# Schaltplan_Power_Amp.net
KiCad netlist of a schematic drawn in EAGLE
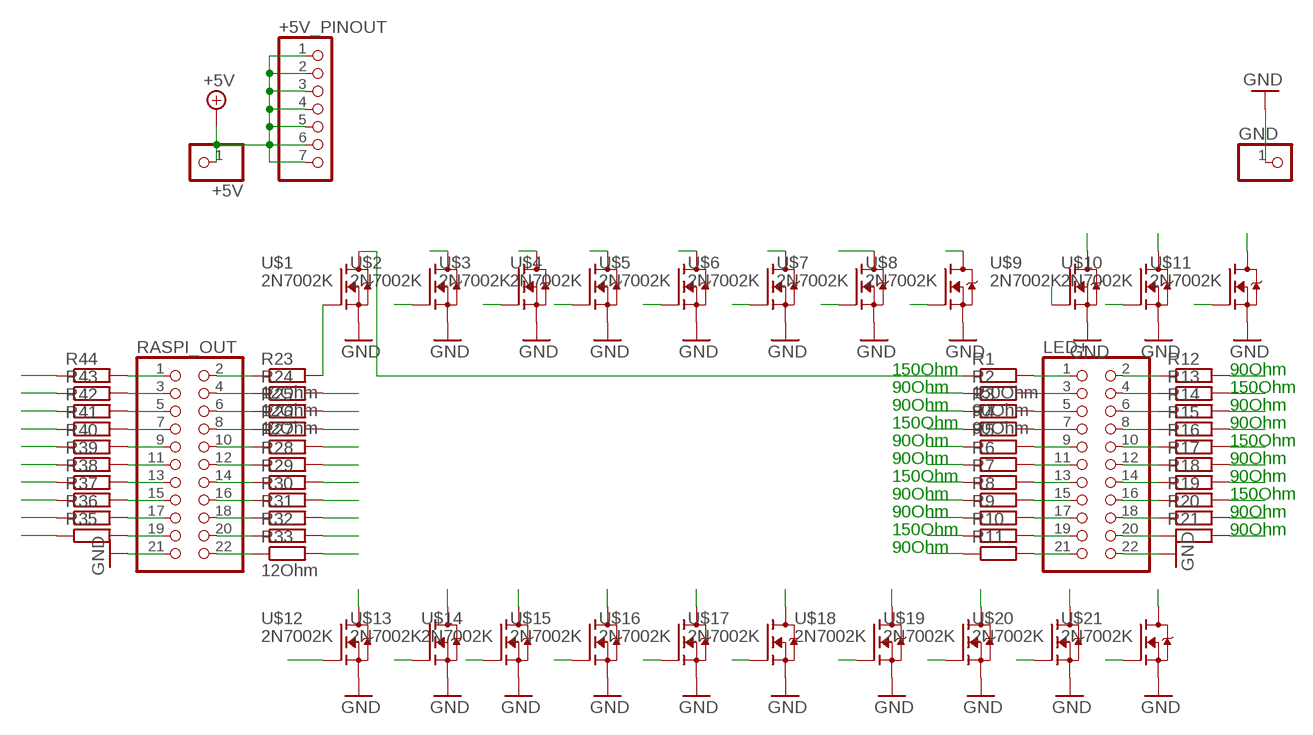
[diagram p0: schematic, sheet 1]

(export (version "E")
  (design (tool "Eeschema 10.0.6"))
  (components
    (comp (ref "+5V")
      (value "PINHD-1X1")
      (footprint "eagle-import:1X01")
      (libsource (lib "eagle-import") (part "PINHD-1X1"))
    )
    (comp (ref "+5V_PINOUT")
      (value "PINHD-1X7")
      (footprint "eagle-import:1X07")
      (libsource (lib "eagle-import") (part "PINHD-1X7"))
    )
    (comp (ref "GND")
      (value "PINHD-1X1")
      (footprint "eagle-import:1X01")
      (libsource (lib "eagle-import") (part "PINHD-1X1"))
    )
    (comp (ref "LED+")
      (value "PINHD-2X11")
      (footprint "eagle-import:2X11")
      (libsource (lib "eagle-import") (part "PINHD-2X11"))
    )
    (comp (ref "R1")
      (value "150Ohm")
      (footprint "eagle-import:M1206")
      (libsource (lib "eagle-import") (part "R-EU_M1206"))
    )
    (comp (ref "R2")
      (value "90Ohm")
      (footprint "eagle-import:M1206")
      (libsource (lib "eagle-import") (part "R-EU_M1206"))
    )
    (comp (ref "R3")
      (value "90Ohm")
      (footprint "eagle-import:M1206")
      (libsource (lib "eagle-import") (part "R-EU_M1206"))
    )
    (comp (ref "R4")
      (value "R-EU_M1206")
      (footprint "eagle-import:M1206")
      (libsource (lib "eagle-import") (part "R-EU_M1206"))
    )
    (comp (ref "R5")
      (value "R-EU_M1206")
      (footprint "eagle-import:M1206")
      (libsource (lib "eagle-import") (part "R-EU_M1206"))
    )
    (comp (ref "R6")
      (value "R-EU_M1206")
      (footprint "eagle-import:M1206")
      (libsource (lib "eagle-import") (part "R-EU_M1206"))
    )
    (comp (ref "R7")
      (value "R-EU_M1206")
      (footprint "eagle-import:M1206")
      (libsource (lib "eagle-import") (part "R-EU_M1206"))
    )
    (comp (ref "R8")
      (value "R-EU_M1206")
      (footprint "eagle-import:M1206")
      (libsource (lib "eagle-import") (part "R-EU_M1206"))
    )
    (comp (ref "R9")
      (value "R-EU_M1206")
      (footprint "eagle-import:M1206")
      (libsource (lib "eagle-import") (part "R-EU_M1206"))
    )
    (comp (ref "R10")
      (value "R-EU_M1206")
      (footprint "eagle-import:M1206")
      (libsource (lib "eagle-import") (part "R-EU_M1206"))
    )
    (comp (ref "R11")
      (value "R-EU_M1206")
      (footprint "eagle-import:M1206")
      (libsource (lib "eagle-import") (part "R-EU_M1206"))
    )
    (comp (ref "R12")
      (value "R-EU_M1206")
      (footprint "eagle-import:M1206")
      (libsource (lib "eagle-import") (part "R-EU_M1206"))
    )
    (comp (ref "R13")
      (value "R-EU_M1206")
      (footprint "eagle-import:M1206")
      (libsource (lib "eagle-import") (part "R-EU_M1206"))
    )
    (comp (ref "R14")
      (value "R-EU_M1206")
      (footprint "eagle-import:M1206")
      (libsource (lib "eagle-import") (part "R-EU_M1206"))
    )
    (comp (ref "R15")
      (value "R-EU_M1206")
      (footprint "eagle-import:M1206")
      (libsource (lib "eagle-import") (part "R-EU_M1206"))
    )
    (comp (ref "R16")
      (value "R-EU_M1206")
      (footprint "eagle-import:M1206")
      (libsource (lib "eagle-import") (part "R-EU_M1206"))
    )
    (comp (ref "R17")
      (value "R-EU_M1206")
      (footprint "eagle-import:M1206")
      (libsource (lib "eagle-import") (part "R-EU_M1206"))
    )
    (comp (ref "R18")
      (value "R-EU_M1206")
      (footprint "eagle-import:M1206")
      (libsource (lib "eagle-import") (part "R-EU_M1206"))
    )
    (comp (ref "R19")
      (value "R-EU_M1206")
      (footprint "eagle-import:M1206")
      (libsource (lib "eagle-import") (part "R-EU_M1206"))
    )
    (comp (ref "R20")
      (value "R-EU_M1206")
      (footprint "eagle-import:M1206")
      (libsource (lib "eagle-import") (part "R-EU_M1206"))
    )
    (comp (ref "R21")
      (value "R-EU_M1206")
      (footprint "eagle-import:M1206")
      (libsource (lib "eagle-import") (part "R-EU_M1206"))
    )
    (comp (ref "R23")
      (value "12Ohm")
      (footprint "eagle-import:M1206")
      (libsource (lib "eagle-import") (part "R-EU_M1206"))
    )
    (comp (ref "R24")
      (value "12Ohm")
      (footprint "eagle-import:M1206")
      (libsource (lib "eagle-import") (part "R-EU_M1206"))
    )
    (comp (ref "R25")
      (value "12Ohm")
      (footprint "eagle-import:M1206")
      (libsource (lib "eagle-import") (part "R-EU_M1206"))
    )
    (comp (ref "R26")
      (value "R-EU_M1206")
      (footprint "eagle-import:M1206")
      (libsource (lib "eagle-import") (part "R-EU_M1206"))
    )
    (comp (ref "R27")
      (value "R-EU_M1206")
      (footprint "eagle-import:M1206")
      (libsource (lib "eagle-import") (part "R-EU_M1206"))
    )
    (comp (ref "R28")
      (value "R-EU_M1206")
      (footprint "eagle-import:M1206")
      (libsource (lib "eagle-import") (part "R-EU_M1206"))
    )
    (comp (ref "R29")
      (value "R-EU_M1206")
      (footprint "eagle-import:M1206")
      (libsource (lib "eagle-import") (part "R-EU_M1206"))
    )
    (comp (ref "R30")
      (value "R-EU_M1206")
      (footprint "eagle-import:M1206")
      (libsource (lib "eagle-import") (part "R-EU_M1206"))
    )
    (comp (ref "R31")
      (value "R-EU_M1206")
      (footprint "eagle-import:M1206")
      (libsource (lib "eagle-import") (part "R-EU_M1206"))
    )
    (comp (ref "R32")
      (value "R-EU_M1206")
      (footprint "eagle-import:M1206")
      (libsource (lib "eagle-import") (part "R-EU_M1206"))
    )
    (comp (ref "R33")
      (value "12Ohm")
      (footprint "eagle-import:M1206")
      (libsource (lib "eagle-import") (part "R-EU_M1206"))
    )
    (comp (ref "R35")
      (value "R-EU_M1206")
      (footprint "eagle-import:M1206")
      (libsource (lib "eagle-import") (part "R-EU_M1206"))
    )
    (comp (ref "R36")
      (value "R-EU_M1206")
      (footprint "eagle-import:M1206")
      (libsource (lib "eagle-import") (part "R-EU_M1206"))
    )
    (comp (ref "R37")
      (value "R-EU_M1206")
      (footprint "eagle-import:M1206")
      (libsource (lib "eagle-import") (part "R-EU_M1206"))
    )
    (comp (ref "R38")
      (value "R-EU_M1206")
      (footprint "eagle-import:M1206")
      (libsource (lib "eagle-import") (part "R-EU_M1206"))
    )
    (comp (ref "R39")
      (value "R-EU_M1206")
      (footprint "eagle-import:M1206")
      (libsource (lib "eagle-import") (part "R-EU_M1206"))
    )
    (comp (ref "R40")
      (value "R-EU_M1206")
      (footprint "eagle-import:M1206")
      (libsource (lib "eagle-import") (part "R-EU_M1206"))
    )
    (comp (ref "R41")
      (value "R-EU_M1206")
      (footprint "eagle-import:M1206")
      (libsource (lib "eagle-import") (part "R-EU_M1206"))
    )
    (comp (ref "R42")
      (value "R-EU_M1206")
      (footprint "eagle-import:M1206")
      (libsource (lib "eagle-import") (part "R-EU_M1206"))
    )
    (comp (ref "R43")
      (value "R-EU_M1206")
      (footprint "eagle-import:M1206")
      (libsource (lib "eagle-import") (part "R-EU_M1206"))
    )
    (comp (ref "R44")
      (value "R-EU_M1206")
      (footprint "eagle-import:M1206")
      (libsource (lib "eagle-import") (part "R-EU_M1206"))
    )
    (comp (ref "RASPI_OUT")
      (value "PINHD-2X11")
      (footprint "eagle-import:2X11")
      (libsource (lib "eagle-import") (part "PINHD-2X11"))
    )
    (comp (ref "U$1")
      (value "2N7002K")
      (footprint "eagle-import:SOT23")
      (libsource (lib "eagle-import") (part "2N7002K"))
    )
    (comp (ref "U$2")
      (value "2N7002K")
      (footprint "eagle-import:SOT23")
      (libsource (lib "eagle-import") (part "2N7002K"))
    )
    (comp (ref "U$3")
      (value "2N7002K")
      (footprint "eagle-import:SOT23")
      (libsource (lib "eagle-import") (part "2N7002K"))
    )
    (comp (ref "U$4")
      (value "2N7002K")
      (footprint "eagle-import:SOT23")
      (libsource (lib "eagle-import") (part "2N7002K"))
    )
    (comp (ref "U$5")
      (value "2N7002K")
      (footprint "eagle-import:SOT23")
      (libsource (lib "eagle-import") (part "2N7002K"))
    )
    (comp (ref "U$6")
      (value "2N7002K")
      (footprint "eagle-import:SOT23")
      (libsource (lib "eagle-import") (part "2N7002K"))
    )
    (comp (ref "U$7")
      (value "2N7002K")
      (footprint "eagle-import:SOT23")
      (libsource (lib "eagle-import") (part "2N7002K"))
    )
    (comp (ref "U$8")
      (value "2N7002K")
      (footprint "eagle-import:SOT23")
      (libsource (lib "eagle-import") (part "2N7002K"))
    )
    (comp (ref "U$9")
      (value "2N7002K")
      (footprint "eagle-import:SOT23")
      (libsource (lib "eagle-import") (part "2N7002K"))
    )
    (comp (ref "U$10")
      (value "2N7002K")
      (footprint "eagle-import:SOT23")
      (libsource (lib "eagle-import") (part "2N7002K"))
    )
    (comp (ref "U$11")
      (value "2N7002K")
      (footprint "eagle-import:SOT23")
      (libsource (lib "eagle-import") (part "2N7002K"))
    )
    (comp (ref "U$12")
      (value "2N7002K")
      (footprint "eagle-import:SOT23")
      (libsource (lib "eagle-import") (part "2N7002K"))
    )
    (comp (ref "U$13")
      (value "2N7002K")
      (footprint "eagle-import:SOT23")
      (libsource (lib "eagle-import") (part "2N7002K"))
    )
    (comp (ref "U$14")
      (value "2N7002K")
      (footprint "eagle-import:SOT23")
      (libsource (lib "eagle-import") (part "2N7002K"))
    )
    (comp (ref "U$15")
      (value "2N7002K")
      (footprint "eagle-import:SOT23")
      (libsource (lib "eagle-import") (part "2N7002K"))
    )
    (comp (ref "U$16")
      (value "2N7002K")
      (footprint "eagle-import:SOT23")
      (libsource (lib "eagle-import") (part "2N7002K"))
    )
    (comp (ref "U$17")
      (value "2N7002K")
      (footprint "eagle-import:SOT23")
      (libsource (lib "eagle-import") (part "2N7002K"))
    )
    (comp (ref "U$18")
      (value "2N7002K")
      (footprint "eagle-import:SOT23")
      (libsource (lib "eagle-import") (part "2N7002K"))
    )
    (comp (ref "U$19")
      (value "2N7002K")
      (footprint "eagle-import:SOT23")
      (libsource (lib "eagle-import") (part "2N7002K"))
    )
    (comp (ref "U$20")
      (value "2N7002K")
      (footprint "eagle-import:SOT23")
      (libsource (lib "eagle-import") (part "2N7002K"))
    )
    (comp (ref "U$21")
      (value "2N7002K")
      (footprint "eagle-import:SOT23")
      (libsource (lib "eagle-import") (part "2N7002K"))
    )
  )
  (nets
    (net (code "1") (name "+5V") (class "Default")
      (node (ref "+5V") (pin "1") (pinfunction "1_1") (pintype "passive"))
      (node (ref "+5V_PINOUT") (pin "1") (pinfunction "1_1") (pintype "passive"))
      (node (ref "+5V_PINOUT") (pin "2") (pinfunction "2_2") (pintype "passive"))
      (node (ref "+5V_PINOUT") (pin "3") (pinfunction "3_3") (pintype "passive"))
      (node (ref "+5V_PINOUT") (pin "4") (pinfunction "4_4") (pintype "passive"))
      (node (ref "+5V_PINOUT") (pin "5") (pinfunction "5_5") (pintype "passive"))
      (node (ref "+5V_PINOUT") (pin "6") (pinfunction "6_6") (pintype "passive"))
      (node (ref "+5V_PINOUT") (pin "7") (pinfunction "7_7") (pintype "passive"))
    )
    (net (code "2") (name "/DRAIN2") (class "Default")
      (node (ref "R2") (pin "1") (pinfunction "1_1") (pintype "passive"))
      (node (ref "U$2") (pin "3") (pinfunction "D_3") (pintype "passive"))
    )
    (net (code "3") (name "/DRAIN3") (class "Default")
      (node (ref "R3") (pin "1") (pinfunction "1_1") (pintype "passive"))
      (node (ref "U$3") (pin "3") (pinfunction "D_3") (pintype "passive"))
    )
    (net (code "4") (name "/DRAIN4") (class "Default")
      (node (ref "R4") (pin "1") (pinfunction "1_1") (pintype "passive"))
      (node (ref "U$4") (pin "3") (pinfunction "D_3") (pintype "passive"))
    )
    (net (code "5") (name "/DRAIN5") (class "Default")
      (node (ref "R5") (pin "1") (pinfunction "1_1") (pintype "passive"))
      (node (ref "U$5") (pin "3") (pinfunction "D_3") (pintype "passive"))
    )
    (net (code "6") (name "/DRAIN6") (class "Default")
      (node (ref "R6") (pin "1") (pinfunction "1_1") (pintype "passive"))
      (node (ref "U$6") (pin "3") (pinfunction "D_3") (pintype "passive"))
    )
    (net (code "7") (name "/DRAIN7") (class "Default")
      (node (ref "R7") (pin "1") (pinfunction "1_1") (pintype "passive"))
      (node (ref "U$7") (pin "3") (pinfunction "D_3") (pintype "passive"))
    )
    (net (code "8") (name "/DRAIN8") (class "Default")
      (node (ref "R8") (pin "1") (pinfunction "1_1") (pintype "passive"))
      (node (ref "U$8") (pin "3") (pinfunction "D_3") (pintype "passive"))
    )
    (net (code "9") (name "/DRAIN9") (class "Default")
      (node (ref "R9") (pin "1") (pinfunction "1_1") (pintype "passive"))
      (node (ref "U$9") (pin "3") (pinfunction "D_3") (pintype "passive"))
    )
    (net (code "10") (name "/DRAIN10") (class "Default")
      (node (ref "R10") (pin "1") (pinfunction "1_1") (pintype "passive"))
      (node (ref "U$10") (pin "3") (pinfunction "D_3") (pintype "passive"))
    )
    (net (code "11") (name "/DRAIN11") (class "Default")
      (node (ref "R11") (pin "1") (pinfunction "1_1") (pintype "passive"))
      (node (ref "U$11") (pin "3") (pinfunction "D_3") (pintype "passive"))
    )
    (net (code "12") (name "/DRAIN12") (class "Default")
      (node (ref "R12") (pin "2") (pinfunction "2_2") (pintype "passive"))
      (node (ref "U$12") (pin "3") (pinfunction "D_3") (pintype "passive"))
    )
    (net (code "13") (name "/DRAIN13") (class "Default")
      (node (ref "R13") (pin "2") (pinfunction "2_2") (pintype "passive"))
      (node (ref "U$13") (pin "3") (pinfunction "D_3") (pintype "passive"))
    )
    (net (code "14") (name "/DRAIN14") (class "Default")
      (node (ref "R14") (pin "2") (pinfunction "2_2") (pintype "passive"))
      (node (ref "U$14") (pin "3") (pinfunction "D_3") (pintype "passive"))
    )
    (net (code "15") (name "/DRAIN15") (class "Default")
      (node (ref "R15") (pin "2") (pinfunction "2_2") (pintype "passive"))
      (node (ref "U$15") (pin "3") (pinfunction "D_3") (pintype "passive"))
    )
    (net (code "16") (name "/DRAIN16") (class "Default")
      (node (ref "R16") (pin "2") (pinfunction "2_2") (pintype "passive"))
      (node (ref "U$16") (pin "3") (pinfunction "D_3") (pintype "passive"))
    )
    (net (code "17") (name "/DRAIN17") (class "Default")
      (node (ref "R17") (pin "2") (pinfunction "2_2") (pintype "passive"))
      (node (ref "U$17") (pin "3") (pinfunction "D_3") (pintype "passive"))
    )
    (net (code "18") (name "/DRAIN18") (class "Default")
      (node (ref "R18") (pin "2") (pinfunction "2_2") (pintype "passive"))
      (node (ref "U$18") (pin "3") (pinfunction "D_3") (pintype "passive"))
    )
    (net (code "19") (name "/DRAIN19") (class "Default")
      (node (ref "R19") (pin "2") (pinfunction "2_2") (pintype "passive"))
      (node (ref "U$19") (pin "3") (pinfunction "D_3") (pintype "passive"))
    )
    (net (code "20") (name "/DRAIN20") (class "Default")
      (node (ref "R20") (pin "2") (pinfunction "2_2") (pintype "passive"))
      (node (ref "U$20") (pin "3") (pinfunction "D_3") (pintype "passive"))
    )
    (net (code "21") (name "/DRAIN21") (class "Default")
      (node (ref "R21") (pin "2") (pinfunction "2_2") (pintype "passive"))
      (node (ref "U$21") (pin "3") (pinfunction "D_3") (pintype "passive"))
    )
    (net (code "22") (name "/GATE2") (class "Default")
      (node (ref "R24") (pin "2") (pinfunction "2_2") (pintype "passive"))
      (node (ref "U$2") (pin "1") (pinfunction "G_1") (pintype "passive"))
    )
    (net (code "23") (name "/GATE3") (class "Default")
      (node (ref "R25") (pin "2") (pinfunction "2_2") (pintype "passive"))
      (node (ref "U$3") (pin "1") (pinfunction "G_1") (pintype "passive"))
    )
    (net (code "24") (name "/GATE4") (class "Default")
      (node (ref "R26") (pin "2") (pinfunction "2_2") (pintype "passive"))
      (node (ref "U$4") (pin "1") (pinfunction "G_1") (pintype "passive"))
    )
    (net (code "25") (name "/GATE5") (class "Default")
      (node (ref "R27") (pin "2") (pinfunction "2_2") (pintype "passive"))
      (node (ref "U$5") (pin "1") (pinfunction "G_1") (pintype "passive"))
    )
    (net (code "26") (name "/GATE6") (class "Default")
      (node (ref "R28") (pin "2") (pinfunction "2_2") (pintype "passive"))
      (node (ref "U$6") (pin "1") (pinfunction "G_1") (pintype "passive"))
    )
    (net (code "27") (name "/GATE7") (class "Default")
      (node (ref "R29") (pin "2") (pinfunction "2_2") (pintype "passive"))
      (node (ref "U$7") (pin "1") (pinfunction "G_1") (pintype "passive"))
    )
    (net (code "28") (name "/GATE8") (class "Default")
      (node (ref "R30") (pin "2") (pinfunction "2_2") (pintype "passive"))
      (node (ref "U$8") (pin "1") (pinfunction "G_1") (pintype "passive"))
    )
    (net (code "29") (name "/GATE9") (class "Default")
      (node (ref "R31") (pin "2") (pinfunction "2_2") (pintype "passive"))
      (node (ref "U$9") (pin "1") (pinfunction "G_1") (pintype "passive"))
    )
    (net (code "30") (name "/GATE10") (class "Default")
      (node (ref "R32") (pin "2") (pinfunction "2_2") (pintype "passive"))
      (node (ref "U$10") (pin "1") (pinfunction "G_1") (pintype "passive"))
    )
    (net (code "31") (name "/GATE11") (class "Default")
      (node (ref "R33") (pin "2") (pinfunction "2_2") (pintype "passive"))
      (node (ref "U$11") (pin "1") (pinfunction "G_1") (pintype "passive"))
    )
    (net (code "32") (name "/GATE12") (class "Default")
      (node (ref "R44") (pin "1") (pinfunction "1_1") (pintype "passive"))
      (node (ref "U$12") (pin "1") (pinfunction "G_1") (pintype "passive"))
    )
    (net (code "33") (name "/GATE13") (class "Default")
      (node (ref "R43") (pin "1") (pinfunction "1_1") (pintype "passive"))
      (node (ref "U$13") (pin "1") (pinfunction "G_1") (pintype "passive"))
    )
    (net (code "34") (name "/GATE14") (class "Default")
      (node (ref "R42") (pin "1") (pinfunction "1_1") (pintype "passive"))
      (node (ref "U$14") (pin "1") (pinfunction "G_1") (pintype "passive"))
    )
    (net (code "35") (name "/GATE15") (class "Default")
      (node (ref "R41") (pin "1") (pinfunction "1_1") (pintype "passive"))
      (node (ref "U$15") (pin "1") (pinfunction "G_1") (pintype "passive"))
    )
    (net (code "36") (name "/GATE16") (class "Default")
      (node (ref "R40") (pin "1") (pinfunction "1_1") (pintype "passive"))
      (node (ref "U$16") (pin "1") (pinfunction "G_1") (pintype "passive"))
    )
    (net (code "37") (name "/GATE17") (class "Default")
      (node (ref "R39") (pin "1") (pinfunction "1_1") (pintype "passive"))
      (node (ref "U$17") (pin "1") (pinfunction "G_1") (pintype "passive"))
    )
    (net (code "38") (name "/GATE18") (class "Default")
      (node (ref "R38") (pin "1") (pinfunction "1_1") (pintype "passive"))
      (node (ref "U$18") (pin "1") (pinfunction "G_1") (pintype "passive"))
    )
    (net (code "39") (name "/GATE19") (class "Default")
      (node (ref "R37") (pin "1") (pinfunction "1_1") (pintype "passive"))
      (node (ref "U$19") (pin "1") (pinfunction "G_1") (pintype "passive"))
    )
    (net (code "40") (name "/GATE20") (class "Default")
      (node (ref "R36") (pin "1") (pinfunction "1_1") (pintype "passive"))
      (node (ref "U$20") (pin "1") (pinfunction "G_1") (pintype "passive"))
    )
    (net (code "41") (name "/GATE21") (class "Default")
      (node (ref "R35") (pin "1") (pinfunction "1_1") (pintype "passive"))
      (node (ref "U$21") (pin "1") (pinfunction "G_1") (pintype "passive"))
    )
    (net (code "42") (name "GND") (class "Default")
      (node (ref "GND") (pin "1") (pinfunction "1_1") (pintype "passive"))
      (node (ref "LED+") (pin "22") (pinfunction "22_22") (pintype "passive"))
      (node (ref "RASPI_OUT") (pin "21") (pinfunction "21_21") (pintype "passive"))
      (node (ref "U$1") (pin "2") (pinfunction "S_2") (pintype "passive"))
      (node (ref "U$10") (pin "2") (pinfunction "S_2") (pintype "passive"))
      (node (ref "U$11") (pin "2") (pinfunction "S_2") (pintype "passive"))
      (node (ref "U$12") (pin "2") (pinfunction "S_2") (pintype "passive"))
      (node (ref "U$13") (pin "2") (pinfunction "S_2") (pintype "passive"))
      (node (ref "U$14") (pin "2") (pinfunction "S_2") (pintype "passive"))
      (node (ref "U$15") (pin "2") (pinfunction "S_2") (pintype "passive"))
      (node (ref "U$16") (pin "2") (pinfunction "S_2") (pintype "passive"))
      (node (ref "U$17") (pin "2") (pinfunction "S_2") (pintype "passive"))
      (node (ref "U$18") (pin "2") (pinfunction "S_2") (pintype "passive"))
      (node (ref "U$19") (pin "2") (pinfunction "S_2") (pintype "passive"))
      (node (ref "U$2") (pin "2") (pinfunction "S_2") (pintype "passive"))
      (node (ref "U$20") (pin "2") (pinfunction "S_2") (pintype "passive"))
      (node (ref "U$21") (pin "2") (pinfunction "S_2") (pintype "passive"))
      (node (ref "U$3") (pin "2") (pinfunction "S_2") (pintype "passive"))
      (node (ref "U$4") (pin "2") (pinfunction "S_2") (pintype "passive"))
      (node (ref "U$5") (pin "2") (pinfunction "S_2") (pintype "passive"))
      (node (ref "U$6") (pin "2") (pinfunction "S_2") (pintype "passive"))
      (node (ref "U$7") (pin "2") (pinfunction "S_2") (pintype "passive"))
      (node (ref "U$8") (pin "2") (pinfunction "S_2") (pintype "passive"))
      (node (ref "U$9") (pin "2") (pinfunction "S_2") (pintype "passive"))
    )
    (net (code "43") (name "Net-(LED+-Pad1)") (class "Default")
      (node (ref "LED+") (pin "1") (pinfunction "1_1") (pintype "passive"))
      (node (ref "R1") (pin "2") (pinfunction "2_2") (pintype "passive"))
    )
    (net (code "44") (name "Net-(LED+-Pad2)") (class "Default")
      (node (ref "LED+") (pin "2") (pinfunction "2_2") (pintype "passive"))
      (node (ref "R12") (pin "1") (pinfunction "1_1") (pintype "passive"))
    )
    (net (code "45") (name "Net-(LED+-Pad3)") (class "Default")
      (node (ref "LED+") (pin "3") (pinfunction "3_3") (pintype "passive"))
      (node (ref "R2") (pin "2") (pinfunction "2_2") (pintype "passive"))
    )
    (net (code "46") (name "Net-(LED+-Pad4)") (class "Default")
      (node (ref "LED+") (pin "4") (pinfunction "4_4") (pintype "passive"))
      (node (ref "R13") (pin "1") (pinfunction "1_1") (pintype "passive"))
    )
    (net (code "47") (name "Net-(LED+-Pad5)") (class "Default")
      (node (ref "LED+") (pin "5") (pinfunction "5_5") (pintype "passive"))
      (node (ref "R3") (pin "2") (pinfunction "2_2") (pintype "passive"))
    )
    (net (code "48") (name "Net-(LED+-Pad6)") (class "Default")
      (node (ref "LED+") (pin "6") (pinfunction "6_6") (pintype "passive"))
      (node (ref "R14") (pin "1") (pinfunction "1_1") (pintype "passive"))
    )
    (net (code "49") (name "Net-(LED+-Pad7)") (class "Default")
      (node (ref "LED+") (pin "7") (pinfunction "7_7") (pintype "passive"))
      (node (ref "R4") (pin "2") (pinfunction "2_2") (pintype "passive"))
    )
    (net (code "50") (name "Net-(LED+-Pad8)") (class "Default")
      (node (ref "LED+") (pin "8") (pinfunction "8_8") (pintype "passive"))
      (node (ref "R15") (pin "1") (pinfunction "1_1") (pintype "passive"))
    )
    (net (code "51") (name "Net-(LED+-Pad9)") (class "Default")
      (node (ref "LED+") (pin "9") (pinfunction "9_9") (pintype "passive"))
      (node (ref "R5") (pin "2") (pinfunction "2_2") (pintype "passive"))
    )
    (net (code "52") (name "Net-(LED+-Pad10)") (class "Default")
      (node (ref "LED+") (pin "10") (pinfunction "10_10") (pintype "passive"))
      (node (ref "R16") (pin "1") (pinfunction "1_1") (pintype "passive"))
    )
    (net (code "53") (name "Net-(LED+-Pad11)") (class "Default")
      (node (ref "LED+") (pin "11") (pinfunction "11_11") (pintype "passive"))
      (node (ref "R6") (pin "2") (pinfunction "2_2") (pintype "passive"))
    )
    (net (code "54") (name "Net-(LED+-Pad12)") (class "Default")
      (node (ref "LED+") (pin "12") (pinfunction "12_12") (pintype "passive"))
      (node (ref "R17") (pin "1") (pinfunction "1_1") (pintype "passive"))
    )
    (net (code "55") (name "Net-(LED+-Pad13)") (class "Default")
      (node (ref "LED+") (pin "13") (pinfunction "13_13") (pintype "passive"))
      (node (ref "R7") (pin "2") (pinfunction "2_2") (pintype "passive"))
    )
    (net (code "56") (name "Net-(LED+-Pad14)") (class "Default")
      (node (ref "LED+") (pin "14") (pinfunction "14_14") (pintype "passive"))
      (node (ref "R18") (pin "1") (pinfunction "1_1") (pintype "passive"))
    )
    (net (code "57") (name "Net-(LED+-Pad15)") (class "Default")
      (node (ref "LED+") (pin "15") (pinfunction "15_15") (pintype "passive"))
      (node (ref "R8") (pin "2") (pinfunction "2_2") (pintype "passive"))
    )
    (net (code "58") (name "Net-(LED+-Pad16)") (class "Default")
      (node (ref "LED+") (pin "16") (pinfunction "16_16") (pintype "passive"))
      (node (ref "R19") (pin "1") (pinfunction "1_1") (pintype "passive"))
    )
    (net (code "59") (name "Net-(LED+-Pad17)") (class "Default")
      (node (ref "LED+") (pin "17") (pinfunction "17_17") (pintype "passive"))
      (node (ref "R9") (pin "2") (pinfunction "2_2") (pintype "passive"))
    )
    (net (code "60") (name "Net-(LED+-Pad18)") (class "Default")
      (node (ref "LED+") (pin "18") (pinfunction "18_18") (pintype "passive"))
      (node (ref "R20") (pin "1") (pinfunction "1_1") (pintype "passive"))
    )
    (net (code "61") (name "Net-(LED+-Pad19)") (class "Default")
      (node (ref "LED+") (pin "19") (pinfunction "19_19") (pintype "passive"))
      (node (ref "R10") (pin "2") (pinfunction "2_2") (pintype "passive"))
    )
    (net (code "62") (name "Net-(LED+-Pad20)") (class "Default")
      (node (ref "LED+") (pin "20") (pinfunction "20_20") (pintype "passive"))
      (node (ref "R21") (pin "1") (pinfunction "1_1") (pintype "passive"))
    )
    (net (code "63") (name "Net-(LED+-Pad21)") (class "Default")
      (node (ref "LED+") (pin "21") (pinfunction "21_21") (pintype "passive"))
      (node (ref "R11") (pin "2") (pinfunction "2_2") (pintype "passive"))
    )
    (net (code "64") (name "Net-(R23-Pad1)") (class "Default")
      (node (ref "R23") (pin "1") (pinfunction "1_1") (pintype "passive"))
      (node (ref "RASPI_OUT") (pin "2") (pinfunction "2_2") (pintype "passive"))
    )
    (net (code "65") (name "Net-(R24-Pad1)") (class "Default")
      (node (ref "R24") (pin "1") (pinfunction "1_1") (pintype "passive"))
      (node (ref "RASPI_OUT") (pin "4") (pinfunction "4_4") (pintype "passive"))
    )
    (net (code "66") (name "Net-(R25-Pad1)") (class "Default")
      (node (ref "R25") (pin "1") (pinfunction "1_1") (pintype "passive"))
      (node (ref "RASPI_OUT") (pin "6") (pinfunction "6_6") (pintype "passive"))
    )
    (net (code "67") (name "Net-(R26-Pad1)") (class "Default")
      (node (ref "R26") (pin "1") (pinfunction "1_1") (pintype "passive"))
      (node (ref "RASPI_OUT") (pin "8") (pinfunction "8_8") (pintype "passive"))
    )
    (net (code "68") (name "Net-(R27-Pad1)") (class "Default")
      (node (ref "R27") (pin "1") (pinfunction "1_1") (pintype "passive"))
      (node (ref "RASPI_OUT") (pin "10") (pinfunction "10_10") (pintype "passive"))
    )
    (net (code "69") (name "Net-(R28-Pad1)") (class "Default")
      (node (ref "R28") (pin "1") (pinfunction "1_1") (pintype "passive"))
      (node (ref "RASPI_OUT") (pin "12") (pinfunction "12_12") (pintype "passive"))
    )
    (net (code "70") (name "Net-(R29-Pad1)") (class "Default")
      (node (ref "R29") (pin "1") (pinfunction "1_1") (pintype "passive"))
      (node (ref "RASPI_OUT") (pin "14") (pinfunction "14_14") (pintype "passive"))
    )
    (net (code "71") (name "Net-(R30-Pad1)") (class "Default")
      (node (ref "R30") (pin "1") (pinfunction "1_1") (pintype "passive"))
      (node (ref "RASPI_OUT") (pin "16") (pinfunction "16_16") (pintype "passive"))
    )
    (net (code "72") (name "Net-(R31-Pad1)") (class "Default")
      (node (ref "R31") (pin "1") (pinfunction "1_1") (pintype "passive"))
      (node (ref "RASPI_OUT") (pin "18") (pinfunction "18_18") (pintype "passive"))
    )
    (net (code "73") (name "Net-(R32-Pad1)") (class "Default")
      (node (ref "R32") (pin "1") (pinfunction "1_1") (pintype "passive"))
      (node (ref "RASPI_OUT") (pin "20") (pinfunction "20_20") (pintype "passive"))
    )
    (net (code "74") (name "Net-(R33-Pad1)") (class "Default")
      (node (ref "R33") (pin "1") (pinfunction "1_1") (pintype "passive"))
      (node (ref "RASPI_OUT") (pin "22") (pinfunction "22_22") (pintype "passive"))
    )
    (net (code "75") (name "Net-(R35-Pad2)") (class "Default")
      (node (ref "R35") (pin "2") (pinfunction "2_2") (pintype "passive"))
      (node (ref "RASPI_OUT") (pin "19") (pinfunction "19_19") (pintype "passive"))
    )
    (net (code "76") (name "Net-(R36-Pad2)") (class "Default")
      (node (ref "R36") (pin "2") (pinfunction "2_2") (pintype "passive"))
      (node (ref "RASPI_OUT") (pin "17") (pinfunction "17_17") (pintype "passive"))
    )
    (net (code "77") (name "Net-(R37-Pad2)") (class "Default")
      (node (ref "R37") (pin "2") (pinfunction "2_2") (pintype "passive"))
      (node (ref "RASPI_OUT") (pin "15") (pinfunction "15_15") (pintype "passive"))
    )
    (net (code "78") (name "Net-(R38-Pad2)") (class "Default")
      (node (ref "R38") (pin "2") (pinfunction "2_2") (pintype "passive"))
      (node (ref "RASPI_OUT") (pin "13") (pinfunction "13_13") (pintype "passive"))
    )
    (net (code "79") (name "Net-(R39-Pad2)") (class "Default")
      (node (ref "R39") (pin "2") (pinfunction "2_2") (pintype "passive"))
      (node (ref "RASPI_OUT") (pin "11") (pinfunction "11_11") (pintype "passive"))
    )
    (net (code "80") (name "Net-(R40-Pad2)") (class "Default")
      (node (ref "R40") (pin "2") (pinfunction "2_2") (pintype "passive"))
      (node (ref "RASPI_OUT") (pin "9") (pinfunction "9_9") (pintype "passive"))
    )
    (net (code "81") (name "Net-(R41-Pad2)") (class "Default")
      (node (ref "R41") (pin "2") (pinfunction "2_2") (pintype "passive"))
      (node (ref "RASPI_OUT") (pin "7") (pinfunction "7_7") (pintype "passive"))
    )
    (net (code "82") (name "Net-(R42-Pad2)") (class "Default")
      (node (ref "R42") (pin "2") (pinfunction "2_2") (pintype "passive"))
      (node (ref "RASPI_OUT") (pin "5") (pinfunction "5_5") (pintype "passive"))
    )
    (net (code "83") (name "Net-(R43-Pad2)") (class "Default")
      (node (ref "R43") (pin "2") (pinfunction "2_2") (pintype "passive"))
      (node (ref "RASPI_OUT") (pin "3") (pinfunction "3_3") (pintype "passive"))
    )
    (net (code "84") (name "Net-(R44-Pad2)") (class "Default")
      (node (ref "R44") (pin "2") (pinfunction "2_2") (pintype "passive"))
      (node (ref "RASPI_OUT") (pin "1") (pinfunction "1_1") (pintype "passive"))
    )
    (net (code "85") (name "Net-(U$1-D)") (class "Default")
      (node (ref "R1") (pin "1") (pinfunction "1_1") (pintype "passive"))
      (node (ref "U$1") (pin "3") (pinfunction "D_3") (pintype "passive"))
    )
    (net (code "86") (name "Net-(U$1-G)") (class "Default")
      (node (ref "R23") (pin "2") (pinfunction "2_2") (pintype "passive"))
      (node (ref "U$1") (pin "1") (pinfunction "G_1") (pintype "passive"))
    )
  )
)
